# lpm.net
KiCad netlist of a schematic drawn in EAGLE
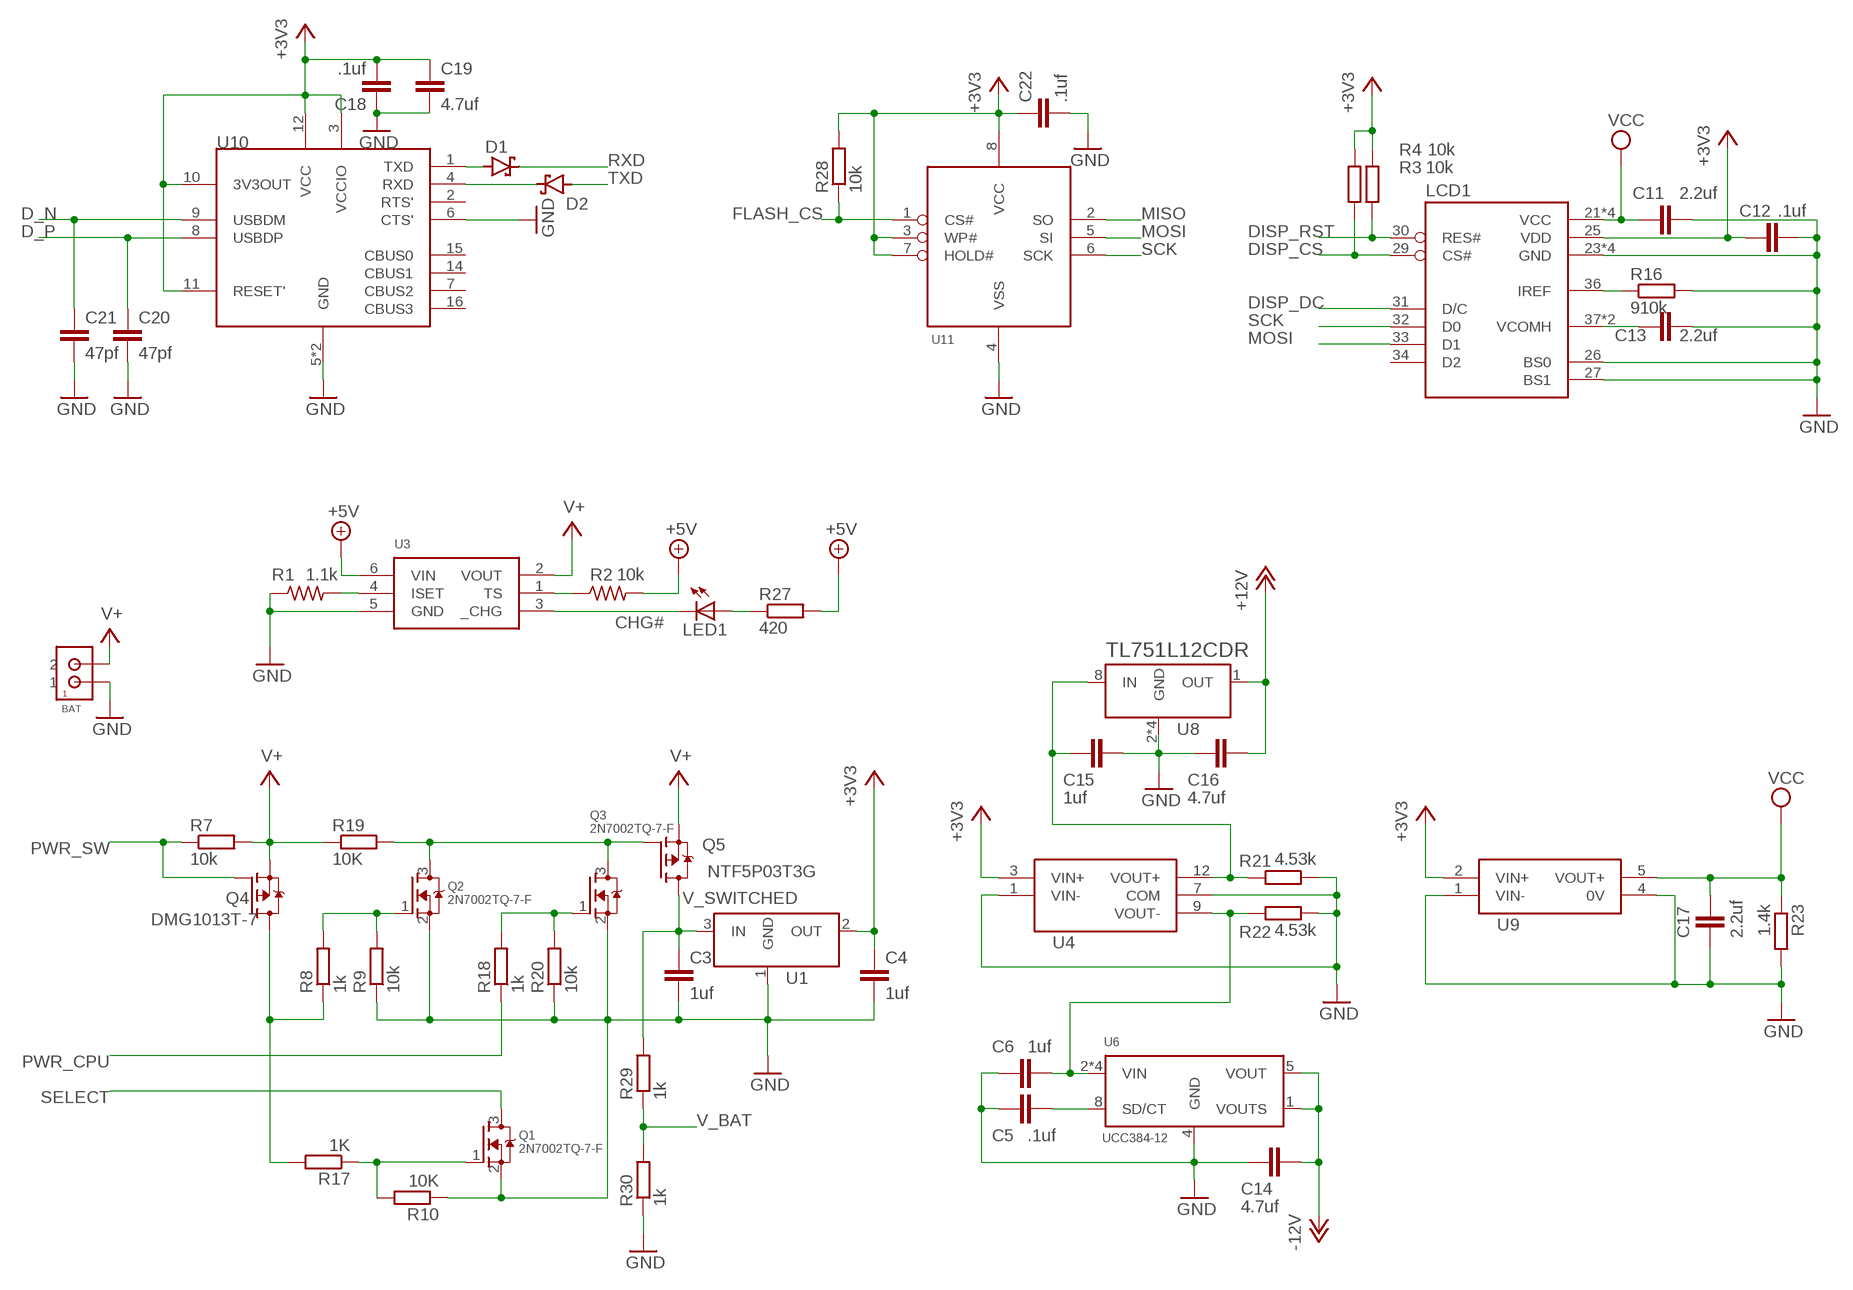
[diagram p0: schematic, sheet 1, part 1 of 2]
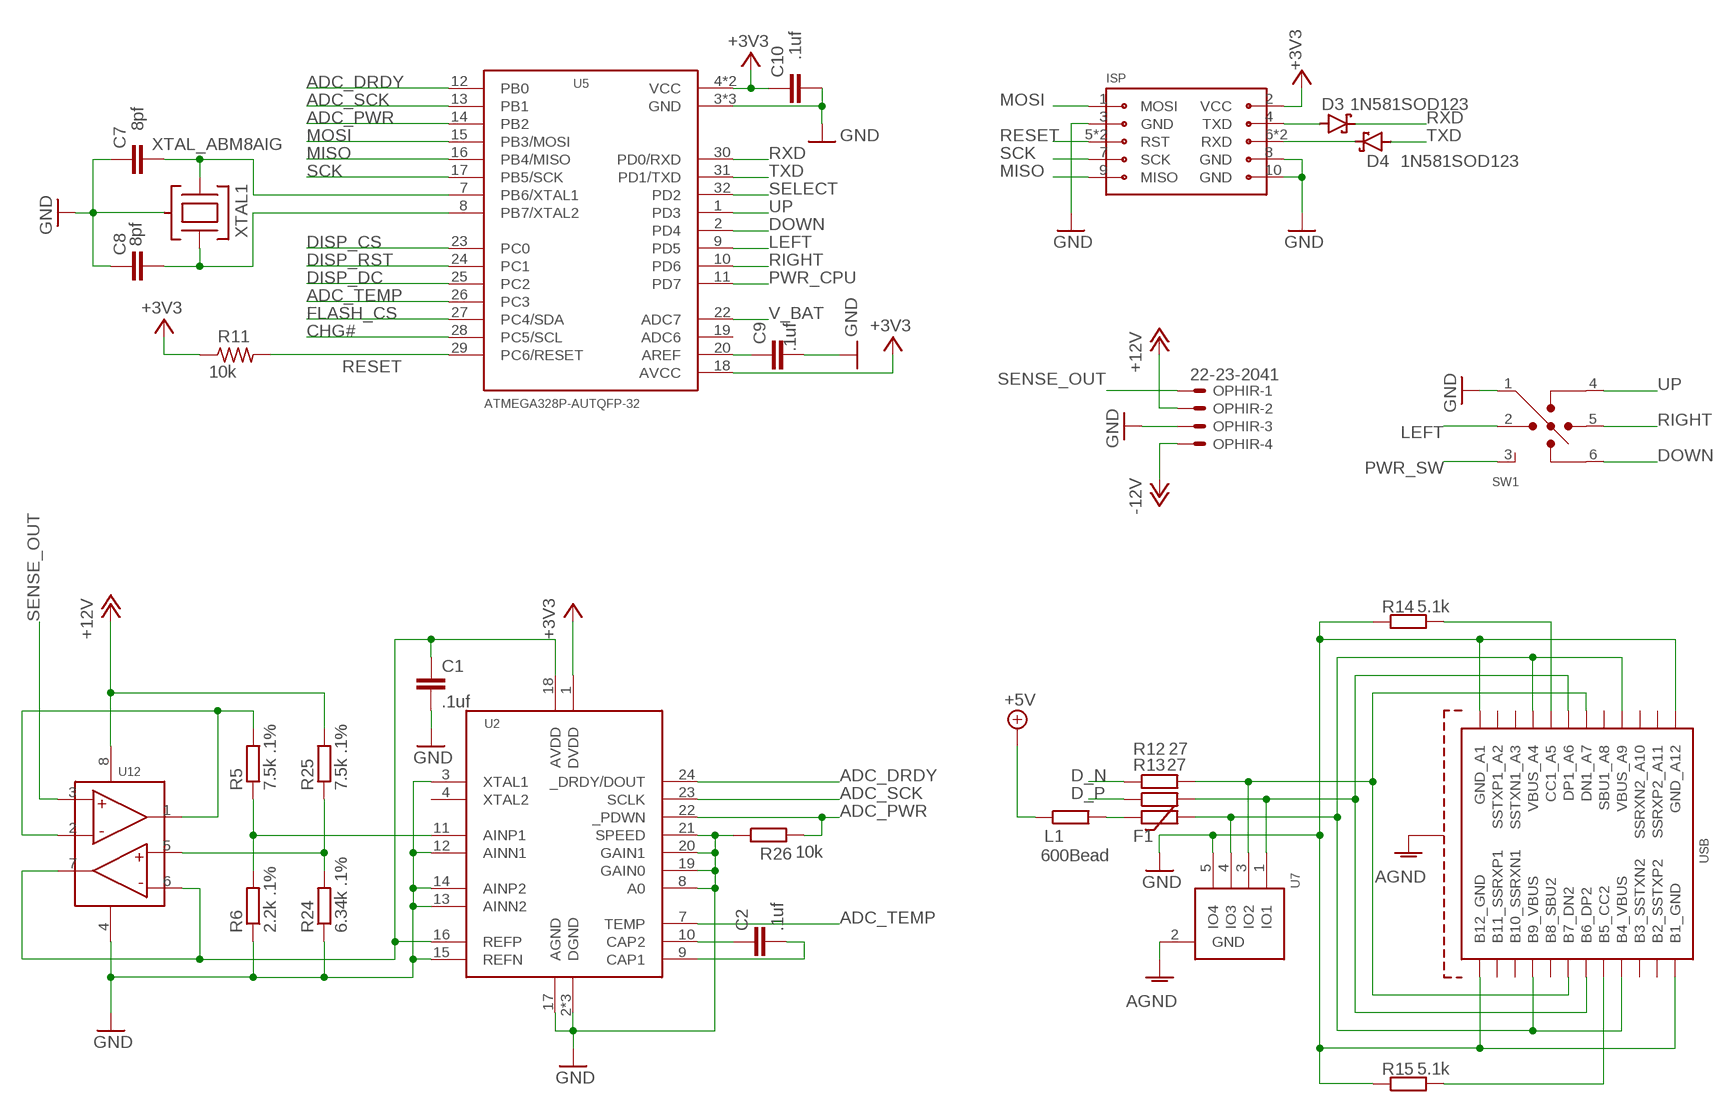
[diagram p1: schematic, sheet 1, part 2 of 2]

(export (version "E")
  (design (tool "Eeschema 10.0.6"))
  (components
    (comp (ref "BAT")
      (value "2PIN_CONNJST_SH")
      (footprint "eagle-import:JST-SM02B-SRSS-TB")
      (libsource (lib "eagle-import") (part "2PIN_CONNJST_SH"))
    )
    (comp (ref "C1")
      (value ".1uf")
      (footprint "eagle-import:C0805")
      (libsource (lib "eagle-import") (part "C-EUC0805"))
    )
    (comp (ref "C2")
      (value ".1uf")
      (footprint "eagle-import:C0805")
      (libsource (lib "eagle-import") (part "C-EUC0805"))
    )
    (comp (ref "C3")
      (value "1uf")
      (footprint "eagle-import:C0805")
      (libsource (lib "eagle-import") (part "C-EUC0805"))
    )
    (comp (ref "C4")
      (value "1uf")
      (footprint "eagle-import:C0805")
      (libsource (lib "eagle-import") (part "C-EUC0805"))
    )
    (comp (ref "C5")
      (value ".1uf")
      (footprint "eagle-import:C0805")
      (libsource (lib "eagle-import") (part "C-EUC0805"))
    )
    (comp (ref "C6")
      (value "1uf")
      (footprint "eagle-import:C0805")
      (libsource (lib "eagle-import") (part "C-EUC0805"))
    )
    (comp (ref "C7")
      (value "8pf")
      (footprint "eagle-import:C0805")
      (libsource (lib "eagle-import") (part "C-EUC0805"))
    )
    (comp (ref "C8")
      (value "8pf")
      (footprint "eagle-import:C0805")
      (libsource (lib "eagle-import") (part "C-EUC0805"))
    )
    (comp (ref "C9")
      (value ".1uf")
      (footprint "eagle-import:C0805")
      (libsource (lib "eagle-import") (part "C-EUC0805"))
    )
    (comp (ref "C10")
      (value ".1uf")
      (footprint "eagle-import:C0805")
      (libsource (lib "eagle-import") (part "C-EUC0805"))
    )
    (comp (ref "C11")
      (value "2.2uf")
      (footprint "eagle-import:C0805")
      (libsource (lib "eagle-import") (part "C-EUC0805"))
    )
    (comp (ref "C12")
      (value ".1uf")
      (footprint "eagle-import:C0805")
      (libsource (lib "eagle-import") (part "C-EUC0805"))
    )
    (comp (ref "C13")
      (value "2.2uf")
      (footprint "eagle-import:C0805")
      (libsource (lib "eagle-import") (part "C-EUC0805"))
    )
    (comp (ref "C14")
      (value "4.7uf")
      (footprint "eagle-import:C0805")
      (libsource (lib "eagle-import") (part "C-EUC0805"))
    )
    (comp (ref "C15")
      (value "1uf")
      (footprint "eagle-import:C0805")
      (libsource (lib "eagle-import") (part "C-EUC0805"))
    )
    (comp (ref "C16")
      (value "4.7uf")
      (footprint "eagle-import:C0805")
      (libsource (lib "eagle-import") (part "C-EUC0805"))
    )
    (comp (ref "C17")
      (value "2.2uf")
      (footprint "eagle-import:C0805")
      (libsource (lib "eagle-import") (part "C-EUC0805"))
    )
    (comp (ref "C18")
      (value ".1uf")
      (footprint "eagle-import:C0805")
      (libsource (lib "eagle-import") (part "C-EUC0805"))
    )
    (comp (ref "C19")
      (value "4.7uf")
      (footprint "eagle-import:C0805")
      (libsource (lib "eagle-import") (part "C-EUC0805"))
    )
    (comp (ref "C20")
      (value "47pf")
      (footprint "eagle-import:C0805")
      (libsource (lib "eagle-import") (part "C-EUC0805"))
    )
    (comp (ref "C21")
      (value "47pf")
      (footprint "eagle-import:C0805")
      (libsource (lib "eagle-import") (part "C-EUC0805"))
    )
    (comp (ref "C22")
      (value ".1uf")
      (footprint "eagle-import:C0805")
      (libsource (lib "eagle-import") (part "C-EUC0805"))
    )
    (comp (ref "D1")
      (value "1N581SOD123")
      (footprint "eagle-import:SOD3715X135")
      (libsource (lib "eagle-import") (part "1N581SOD123"))
    )
    (comp (ref "D2")
      (value "1N581SOD123")
      (footprint "eagle-import:SOD3715X135")
      (libsource (lib "eagle-import") (part "1N581SOD123"))
    )
    (comp (ref "D3")
      (value "1N581SOD123")
      (footprint "eagle-import:SOD3715X135")
      (libsource (lib "eagle-import") (part "1N581SOD123"))
    )
    (comp (ref "D4")
      (value "1N581SOD123")
      (footprint "eagle-import:SOD3715X135")
      (libsource (lib "eagle-import") (part "1N581SOD123"))
    )
    (comp (ref "F1")
      (value "MF-PSHT035KX-2")
      (footprint "eagle-import:FUSC2113X120N")
      (libsource (lib "eagle-import") (part "PTC0805"))
    )
    (comp (ref "ISP")
      (value "10PIN_ISPTC2050")
      (footprint "eagle-import:TC2050-IDC")
      (libsource (lib "eagle-import") (part "10PIN_ISPTC2050"))
    )
    (comp (ref "L1")
      (value "600Bead")
      (footprint "eagle-import:M0805")
      (libsource (lib "eagle-import") (part "R-EU_M0805"))
    )
    (comp (ref "LCD1")
      (value "EAOLEDL128-6")
      (footprint "eagle-import:EAOLEDL128-6")
      (libsource (lib "eagle-import") (part "EAOLEDL128-6"))
    )
    (comp (ref "LED1")
      (value "LEDCHIPLED_0805")
      (footprint "eagle-import:CHIPLED_0805")
      (libsource (lib "eagle-import") (part "LEDCHIPLED_0805"))
    )
    (comp (ref "OPHIR")
      (value "22-23-2041")
      (footprint "eagle-import:22-23-2041")
      (fields (field (name "MF") "MOLEX"))
      (libsource (lib "eagle-import") (part "22-23-2041"))
    )
    (comp (ref "Q1")
      (value "2N7002TQ-7-F")
      (footprint "eagle-import:SOT50P160X80-3")
      (libsource (lib "eagle-import") (part "MOSFET-NSOT-523"))
    )
    (comp (ref "Q2")
      (value "2N7002TQ-7-F")
      (footprint "eagle-import:SOT50P160X80-3")
      (libsource (lib "eagle-import") (part "MOSFET-NSOT-523"))
    )
    (comp (ref "Q3")
      (value "2N7002TQ-7-F")
      (footprint "eagle-import:SOT50P160X80-3")
      (libsource (lib "eagle-import") (part "MOSFET-NSOT-523"))
    )
    (comp (ref "Q4")
      (value "DMG1013T-7")
      (footprint "eagle-import:SOT50P160X80-3")
      (libsource (lib "eagle-import") (part "MOSFET-PSOT-523"))
    )
    (comp (ref "Q5")
      (value "NTF5P03T3G")
      (footprint "eagle-import:SOT230P700X180-4")
      (libsource (lib "eagle-import") (part "MOSFET-PSOT-223"))
    )
    (comp (ref "R1")
      (value "1.1k")
      (footprint "eagle-import:R0805")
      (libsource (lib "eagle-import") (part "R-US_R0805"))
    )
    (comp (ref "R2")
      (value "10k")
      (footprint "eagle-import:R0805")
      (libsource (lib "eagle-import") (part "R-US_R0805"))
    )
    (comp (ref "R3")
      (value "10k")
      (footprint "eagle-import:R0805")
      (libsource (lib "eagle-import") (part "R-EU_R0805"))
    )
    (comp (ref "R4")
      (value "10k")
      (footprint "eagle-import:R0805")
      (libsource (lib "eagle-import") (part "R-EU_R0805"))
    )
    (comp (ref "R5")
      (value "7.5k .1%")
      (footprint "eagle-import:R0805")
      (libsource (lib "eagle-import") (part "R-EU_R0805"))
    )
    (comp (ref "R6")
      (value "2.2k .1%")
      (footprint "eagle-import:R0805")
      (libsource (lib "eagle-import") (part "R-EU_R0805"))
    )
    (comp (ref "R7")
      (value "10k")
      (footprint "eagle-import:R0805")
      (libsource (lib "eagle-import") (part "R-EU_R0805"))
    )
    (comp (ref "R8")
      (value "1k")
      (footprint "eagle-import:R0805")
      (libsource (lib "eagle-import") (part "R-EU_R0805"))
    )
    (comp (ref "R9")
      (value "10k")
      (footprint "eagle-import:R0805")
      (libsource (lib "eagle-import") (part "R-EU_R0805"))
    )
    (comp (ref "R10")
      (value "10K")
      (footprint "eagle-import:R0805")
      (libsource (lib "eagle-import") (part "R-EU_R0805"))
    )
    (comp (ref "R11")
      (value "10k")
      (footprint "eagle-import:R0805")
      (libsource (lib "eagle-import") (part "R-US_R0805"))
    )
    (comp (ref "R12")
      (value "27")
      (footprint "eagle-import:M0805")
      (libsource (lib "eagle-import") (part "R-EU_M0805"))
    )
    (comp (ref "R13")
      (value "27")
      (footprint "eagle-import:M0805")
      (libsource (lib "eagle-import") (part "R-EU_M0805"))
    )
    (comp (ref "R14")
      (value "5.1k")
      (footprint "eagle-import:M0805")
      (libsource (lib "eagle-import") (part "R-EU_M0805"))
    )
    (comp (ref "R15")
      (value "5.1k")
      (footprint "eagle-import:M0805")
      (libsource (lib "eagle-import") (part "R-EU_M0805"))
    )
    (comp (ref "R16")
      (value "910k")
      (footprint "eagle-import:R0805")
      (libsource (lib "eagle-import") (part "R-EU_R0805"))
    )
    (comp (ref "R17")
      (value "1K")
      (footprint "eagle-import:R0805")
      (libsource (lib "eagle-import") (part "R-EU_R0805"))
    )
    (comp (ref "R18")
      (value "1k")
      (footprint "eagle-import:R0805")
      (libsource (lib "eagle-import") (part "R-EU_R0805"))
    )
    (comp (ref "R19")
      (value "10K")
      (footprint "eagle-import:R0805")
      (libsource (lib "eagle-import") (part "R-EU_R0805"))
    )
    (comp (ref "R20")
      (value "10k")
      (footprint "eagle-import:R0805")
      (libsource (lib "eagle-import") (part "R-EU_R0805"))
    )
    (comp (ref "R21")
      (value "4.53k")
      (footprint "eagle-import:R0805")
      (libsource (lib "eagle-import") (part "R-EU_R0805"))
    )
    (comp (ref "R22")
      (value "4.53k")
      (footprint "eagle-import:R0805")
      (libsource (lib "eagle-import") (part "R-EU_R0805"))
    )
    (comp (ref "R23")
      (value "1.4k")
      (footprint "eagle-import:R0805")
      (libsource (lib "eagle-import") (part "R-EU_R0805"))
    )
    (comp (ref "R24")
      (value "6.34k .1%")
      (footprint "eagle-import:R0805")
      (libsource (lib "eagle-import") (part "R-EU_R0805"))
    )
    (comp (ref "R25")
      (value "7.5k .1%")
      (footprint "eagle-import:R0805")
      (libsource (lib "eagle-import") (part "R-EU_R0805"))
    )
    (comp (ref "R26")
      (value "10k")
      (footprint "eagle-import:R0805")
      (libsource (lib "eagle-import") (part "R-EU_R0805"))
    )
    (comp (ref "R27")
      (value "420")
      (footprint "eagle-import:R0805")
      (libsource (lib "eagle-import") (part "R-EU_R0805"))
    )
    (comp (ref "R28")
      (value "10k")
      (footprint "eagle-import:R0805")
      (libsource (lib "eagle-import") (part "R-EU_R0805"))
    )
    (comp (ref "R29")
      (value "1k")
      (footprint "eagle-import:R0805")
      (libsource (lib "eagle-import") (part "R-EU_R0805"))
    )
    (comp (ref "R30")
      (value "1k")
      (footprint "eagle-import:R0805")
      (libsource (lib "eagle-import") (part "R-EU_R0805"))
    )
    (comp (ref "SW1")
      (value "JS-5208")
      (footprint "eagle-import:JS-5208")
      (libsource (lib "eagle-import") (part "JS-5208"))
    )
    (comp (ref "U1")
      (value "AZ1117E-3.3SOT-223")
      (footprint "eagle-import:SOT230P700X180-4")
      (libsource (lib "eagle-import") (part "AZ1117E-3.3SOT-223"))
    )
    (comp (ref "U2")
      (value "ADS1232")
      (footprint "eagle-import:SOP65P640X120-24")
      (libsource (lib "eagle-import") (part "ADS1232"))
    )
    (comp (ref "U3")
      (value "BQ21040SOT-23")
      (footprint "eagle-import:SOT95P280X145-6")
      (libsource (lib "eagle-import") (part "BQ21040SOT-23"))
    )
    (comp (ref "U4")
      (value "NTA0315MC-R")
      (footprint "eagle-import:NTA0315MC-R")
      (libsource (lib "eagle-import") (part "NTA0315MC-R"))
    )
    (comp (ref "U5")
      (value "ATMEGA328P-AUTQFP-32")
      (footprint "eagle-import:QFP80P887X887X120-32")
      (libsource (lib "eagle-import") (part "ATMEGA328P-AUTQFP-32"))
    )
    (comp (ref "U6")
      (value "UCC384-12")
      (footprint "eagle-import:SOIC127P599X175-8")
      (libsource (lib "eagle-import") (part "UCC384-X"))
    )
    (comp (ref "U7")
      (value "ESDS314")
      (footprint "eagle-import:SOT95P282X145-5")
      (libsource (lib "eagle-import") (part "ESDS314"))
    )
    (comp (ref "U8")
      (value "TL751L12CDR")
      (footprint "eagle-import:SOIC127P599X175-8")
      (libsource (lib "eagle-import") (part "TL751"))
    )
    (comp (ref "U9")
      (value "ISE0312A")
      (footprint "eagle-import:ISE0312A")
      (libsource (lib "eagle-import") (part "ISE312A"))
    )
    (comp (ref "U10")
      (value "FT230XSSOP16")
      (footprint "eagle-import:SOP63P599X175-16")
      (libsource (lib "eagle-import") (part "FT230XSSOP16"))
    )
    (comp (ref "U11")
      (value "NV25640DWHFT3G")
      (footprint "eagle-import:SOIC127P599X175-8")
      (libsource (lib "eagle-import") (part "NV25640SOIC-8"))
    )
    (comp (ref "U12")
      (value "OPA2210VSSOP8")
      (footprint "eagle-import:SOP65P490X110-8")
      (libsource (lib "eagle-import") (part "OPA2210VSSOP8"))
    )
    (comp (ref "USB")
      (value "USBC_FEMALEUJ31-CH-31-SMT-TR")
      (footprint "eagle-import:USBC_UJ31-CH-31-SMT-TR")
      (libsource (lib "eagle-import") (part "USBC_FEMALEUJ31-CH-31-SMT-TR"))
    )
    (comp (ref "XTAL1")
      (value "XTAL_ABM8AIG")
      (footprint "eagle-import:XTAL_SMT_3.2X2.5")
      (libsource (lib "eagle-import") (part "XTAL_ABM8AIG"))
    )
  )
  (nets
    (net (code "1") (name "+3V3") (class "Default")
      (node (ref "C10") (pin "1") (pinfunction "1_1") (pintype "passive"))
      (node (ref "C12") (pin "1") (pinfunction "1_1") (pintype "passive"))
      (node (ref "C18") (pin "2") (pinfunction "2_2") (pintype "passive"))
      (node (ref "C19") (pin "1") (pinfunction "1_1") (pintype "passive"))
      (node (ref "C22") (pin "1") (pinfunction "1_1") (pintype "passive"))
      (node (ref "C4") (pin "1") (pinfunction "1_1") (pintype "passive"))
      (node (ref "ISP") (pin "2") (pinfunction "VCC_2") (pintype "bidirectional"))
      (node (ref "LCD1") (pin "25") (pinfunction "VDD_25") (pintype "power_in"))
      (node (ref "R11") (pin "1") (pinfunction "1_1") (pintype "passive"))
      (node (ref "R28") (pin "2") (pinfunction "2_2") (pintype "passive"))
      (node (ref "R3") (pin "2") (pinfunction "2_2") (pintype "passive"))
      (node (ref "R4") (pin "2") (pinfunction "2_2") (pintype "passive"))
      (node (ref "U1") (pin "2") (pinfunction "OUT_2") (pintype "power_in"))
      (node (ref "U10") (pin "10") (pinfunction "3V3OUT_10") (pintype "bidirectional"))
      (node (ref "U10") (pin "11") (pinfunction "RESET'_11") (pintype "bidirectional"))
      (node (ref "U10") (pin "12") (pinfunction "VCC_12") (pintype "power_in"))
      (node (ref "U10") (pin "3") (pinfunction "VCCIO_3") (pintype "power_in"))
      (node (ref "U11") (pin "3") (pinfunction "WP#_3") (pintype "bidirectional"))
      (node (ref "U11") (pin "7") (pinfunction "HOLD#_7") (pintype "bidirectional"))
      (node (ref "U11") (pin "8") (pinfunction "VCC_8") (pintype "power_in"))
      (node (ref "U2") (pin "1") (pinfunction "DVDD_1") (pintype "power_in"))
      (node (ref "U4") (pin "3") (pinfunction "VIN+_3") (pintype "power_in"))
      (node (ref "U5") (pin "18") (pinfunction "AVCC_18") (pintype "power_in"))
      (node (ref "U5") (pin "4") (pinfunction "VCC_4") (pintype "power_in"))
      (node (ref "U5") (pin "6") (pinfunction "VCC_6") (pintype "power_in"))
      (node (ref "U9") (pin "2") (pinfunction "VIN+_2") (pintype "power_in"))
    )
    (net (code "2") (name "+5V") (class "Default")
      (node (ref "L1") (pin "1") (pinfunction "1_1") (pintype "passive"))
      (node (ref "R2") (pin "2") (pinfunction "2_2") (pintype "passive"))
      (node (ref "R27") (pin "2") (pinfunction "2_2") (pintype "passive"))
      (node (ref "U3") (pin "6") (pinfunction "VIN_6") (pintype "power_in"))
    )
    (net (code "3") (name "+12V") (class "Default")
      (node (ref "C16") (pin "2") (pinfunction "2_2") (pintype "passive"))
      (node (ref "OPHIR") (pin "2") (pinfunction "S_2") (pintype "passive"))
      (node (ref "R25") (pin "2") (pinfunction "2_2") (pintype "passive"))
      (node (ref "U12") (pin "8") (pinfunction "V+_8") (pintype "power_in"))
      (node (ref "U8") (pin "1") (pinfunction "OUT_1") (pintype "power_in"))
    )
    (net (code "4") (name "-12V") (class "Default")
      (node (ref "C14") (pin "2") (pinfunction "2_2") (pintype "passive"))
      (node (ref "OPHIR") (pin "4") (pinfunction "S_4") (pintype "passive"))
      (node (ref "U6") (pin "1") (pinfunction "VOUTS_1") (pintype "bidirectional"))
      (node (ref "U6") (pin "5") (pinfunction "VOUT_5") (pintype "power_in"))
    )
    (net (code "5") (name "/ADC_DRDY") (class "Default")
      (node (ref "U2") (pin "24") (pinfunction "_DRDY/DOUT_24") (pintype "bidirectional"))
      (node (ref "U5") (pin "12") (pinfunction "PB0_12") (pintype "bidirectional"))
    )
    (net (code "6") (name "/ADC_PWR") (class "Default")
      (node (ref "R26") (pin "2") (pinfunction "2_2") (pintype "passive"))
      (node (ref "U2") (pin "22") (pinfunction "_PDWN_22") (pintype "bidirectional"))
      (node (ref "U5") (pin "14") (pinfunction "PB2_14") (pintype "bidirectional"))
    )
    (net (code "7") (name "/ADC_SCK") (class "Default")
      (node (ref "U2") (pin "23") (pinfunction "SCLK_23") (pintype "bidirectional"))
      (node (ref "U5") (pin "13") (pinfunction "PB1_13") (pintype "bidirectional"))
    )
    (net (code "8") (name "/ADC_TEMP") (class "Default")
      (node (ref "U2") (pin "7") (pinfunction "TEMP_7") (pintype "bidirectional"))
      (node (ref "U5") (pin "26") (pinfunction "PC3_26") (pintype "bidirectional"))
    )
    (net (code "9") (name "/CHG#") (class "Default")
      (node (ref "LED1") (pin "C") (pinfunction "C_C") (pintype "passive"))
      (node (ref "U3") (pin "3") (pinfunction "_CHG_3") (pintype "bidirectional"))
      (node (ref "U5") (pin "28") (pinfunction "PC5/SCL_28") (pintype "bidirectional"))
    )
    (net (code "10") (name "/DISP_CS") (class "Default")
      (node (ref "LCD1") (pin "29") (pinfunction "CS#_29") (pintype "bidirectional"))
      (node (ref "R4") (pin "1") (pinfunction "1_1") (pintype "passive"))
      (node (ref "U5") (pin "23") (pinfunction "PC0_23") (pintype "bidirectional"))
    )
    (net (code "11") (name "/DISP_DC") (class "Default")
      (node (ref "LCD1") (pin "31") (pinfunction "D/C_31") (pintype "bidirectional"))
      (node (ref "U5") (pin "25") (pinfunction "PC2_25") (pintype "bidirectional"))
    )
    (net (code "12") (name "/DISP_RST") (class "Default")
      (node (ref "LCD1") (pin "30") (pinfunction "RES#_30") (pintype "bidirectional"))
      (node (ref "R3") (pin "1") (pinfunction "1_1") (pintype "passive"))
      (node (ref "U5") (pin "24") (pinfunction "PC1_24") (pintype "bidirectional"))
    )
    (net (code "13") (name "/DOWN") (class "Default")
      (node (ref "SW1") (pin "6") (pinfunction "D_6") (pintype "bidirectional"))
      (node (ref "U5") (pin "2") (pinfunction "PD4_2") (pintype "bidirectional"))
    )
    (net (code "14") (name "/D_N") (class "Default")
      (node (ref "C21") (pin "1") (pinfunction "1_1") (pintype "passive"))
      (node (ref "R12") (pin "1") (pinfunction "1_1") (pintype "passive"))
      (node (ref "U10") (pin "9") (pinfunction "USBDM_9") (pintype "bidirectional"))
    )
    (net (code "15") (name "/D_P") (class "Default")
      (node (ref "C20") (pin "1") (pinfunction "1_1") (pintype "passive"))
      (node (ref "R13") (pin "1") (pinfunction "1_1") (pintype "passive"))
      (node (ref "U10") (pin "8") (pinfunction "USBDP_8") (pintype "bidirectional"))
    )
    (net (code "16") (name "/FLASH_CS") (class "Default")
      (node (ref "R28") (pin "1") (pinfunction "1_1") (pintype "passive"))
      (node (ref "U11") (pin "1") (pinfunction "CS#_1") (pintype "bidirectional"))
      (node (ref "U5") (pin "27") (pinfunction "PC4/SDA_27") (pintype "bidirectional"))
    )
    (net (code "17") (name "/LEFT") (class "Default")
      (node (ref "SW1") (pin "2") (pinfunction "L_2") (pintype "bidirectional"))
      (node (ref "U5") (pin "9") (pinfunction "PD5_9") (pintype "bidirectional"))
    )
    (net (code "18") (name "/MISO") (class "Default")
      (node (ref "ISP") (pin "9") (pinfunction "MISO_9") (pintype "bidirectional"))
      (node (ref "U11") (pin "2") (pinfunction "SO_2") (pintype "bidirectional"))
      (node (ref "U5") (pin "16") (pinfunction "PB4/MISO_16") (pintype "bidirectional"))
    )
    (net (code "19") (name "/MOSI") (class "Default")
      (node (ref "ISP") (pin "1") (pinfunction "MOSI_1") (pintype "bidirectional"))
      (node (ref "LCD1") (pin "33") (pinfunction "D1_33") (pintype "bidirectional"))
      (node (ref "U11") (pin "5") (pinfunction "SI_5") (pintype "bidirectional"))
      (node (ref "U5") (pin "15") (pinfunction "PB3/MOSI_15") (pintype "bidirectional"))
    )
    (net (code "20") (name "/PWR_CPU") (class "Default")
      (node (ref "R18") (pin "1") (pinfunction "1_1") (pintype "passive"))
      (node (ref "U5") (pin "11") (pinfunction "PD7_11") (pintype "bidirectional"))
    )
    (net (code "21") (name "/PWR_SW") (class "Default")
      (node (ref "Q4") (pin "1") (pinfunction "G_1") (pintype "passive"))
      (node (ref "R7") (pin "1") (pinfunction "1_1") (pintype "passive"))
      (node (ref "SW1") (pin "3") (pinfunction "P_3") (pintype "bidirectional"))
    )
    (net (code "22") (name "/RESET") (class "Default")
      (node (ref "ISP") (pin "5") (pinfunction "RST_5") (pintype "bidirectional"))
      (node (ref "ISP") (pin "L5") (pinfunction "RST_L5") (pintype "bidirectional"))
      (node (ref "R11") (pin "2") (pinfunction "2_2") (pintype "passive"))
      (node (ref "U5") (pin "29") (pinfunction "PC6/RESET_29") (pintype "bidirectional"))
    )
    (net (code "23") (name "/RIGHT") (class "Default")
      (node (ref "SW1") (pin "5") (pinfunction "R_5") (pintype "bidirectional"))
      (node (ref "U5") (pin "10") (pinfunction "PD6_10") (pintype "bidirectional"))
    )
    (net (code "24") (name "/RXD") (class "Default")
      (node (ref "D1") (pin "C") (pinfunction "C_C") (pintype "passive"))
      (node (ref "D3") (pin "C") (pinfunction "C_C") (pintype "passive"))
      (node (ref "U5") (pin "30") (pinfunction "PD0/RXD_30") (pintype "bidirectional"))
    )
    (net (code "25") (name "/SCK") (class "Default")
      (node (ref "ISP") (pin "7") (pinfunction "SCK_7") (pintype "bidirectional"))
      (node (ref "LCD1") (pin "32") (pinfunction "D0_32") (pintype "bidirectional"))
      (node (ref "U11") (pin "6") (pinfunction "SCK_6") (pintype "bidirectional"))
      (node (ref "U5") (pin "17") (pinfunction "PB5/SCK_17") (pintype "bidirectional"))
    )
    (net (code "26") (name "/SELECT") (class "Default")
      (node (ref "Q1") (pin "3") (pinfunction "D_3") (pintype "bidirectional"))
      (node (ref "U5") (pin "32") (pinfunction "PD2_32") (pintype "bidirectional"))
    )
    (net (code "27") (name "/SENSE_OUT") (class "Default")
      (node (ref "OPHIR") (pin "1") (pinfunction "S_1") (pintype "passive"))
      (node (ref "U12") (pin "3") (pinfunction "IN1+_3") (pintype "bidirectional"))
    )
    (net (code "28") (name "/TXD") (class "Default")
      (node (ref "D2") (pin "A") (pinfunction "A_A") (pintype "passive"))
      (node (ref "D4") (pin "A") (pinfunction "A_A") (pintype "passive"))
      (node (ref "U5") (pin "31") (pinfunction "PD1/TXD_31") (pintype "bidirectional"))
    )
    (net (code "29") (name "/UP") (class "Default")
      (node (ref "SW1") (pin "4") (pinfunction "U_4") (pintype "bidirectional"))
      (node (ref "U5") (pin "1") (pinfunction "PD3_1") (pintype "bidirectional"))
    )
    (net (code "30") (name "/V_BAT") (class "Default")
      (node (ref "R29") (pin "1") (pinfunction "1_1") (pintype "passive"))
      (node (ref "R30") (pin "2") (pinfunction "2_2") (pintype "passive"))
      (node (ref "U5") (pin "22") (pinfunction "ADC7_22") (pintype "bidirectional"))
    )
    (net (code "31") (name "/V_SWITCHED") (class "Default")
      (node (ref "C3") (pin "1") (pinfunction "1_1") (pintype "passive"))
      (node (ref "Q5") (pin "2") (pinfunction "D_2") (pintype "passive"))
      (node (ref "Q5") (pin "4") (pinfunction "D_4") (pintype "passive"))
      (node (ref "R29") (pin "2") (pinfunction "2_2") (pintype "passive"))
      (node (ref "U1") (pin "3") (pinfunction "IN_3") (pintype "power_in"))
    )
    (net (code "32") (name "AGND") (class "Default")
      (node (ref "U7") (pin "2") (pinfunction "GND_2") (pintype "power_in"))
      (node (ref "USB") (pin "SHLD@1") (pinfunction "SHLD_SHLD@1") (pintype "power_in"))
      (node (ref "USB") (pin "SHLD@2") (pinfunction "SHLD_SHLD@2") (pintype "power_in"))
      (node (ref "USB") (pin "SHLD@3") (pinfunction "SHLD_SHLD@3") (pintype "power_in"))
      (node (ref "USB") (pin "SHLD@4") (pinfunction "SHLD_SHLD@4") (pintype "power_in"))
      (node (ref "USB") (pin "SHLD@5") (pinfunction "SHLD_SHLD@5") (pintype "power_in"))
      (node (ref "USB") (pin "SHLD@6") (pinfunction "SHLD_SHLD@6") (pintype "power_in"))
      (node (ref "USB") (pin "SHLD@7") (pinfunction "SHLD_SHLD@7") (pintype "power_in"))
      (node (ref "USB") (pin "SHLD@8") (pinfunction "SHLD_SHLD@8") (pintype "power_in"))
    )
    (net (code "33") (name "GND") (class "Default")
      (node (ref "BAT") (pin "1") (pinfunction "1_1") (pintype "bidirectional"))
      (node (ref "C1") (pin "2") (pinfunction "2_2") (pintype "passive"))
      (node (ref "C10") (pin "2") (pinfunction "2_2") (pintype "passive"))
      (node (ref "C11") (pin "2") (pinfunction "2_2") (pintype "passive"))
      (node (ref "C12") (pin "2") (pinfunction "2_2") (pintype "passive"))
      (node (ref "C13") (pin "2") (pinfunction "2_2") (pintype "passive"))
      (node (ref "C14") (pin "1") (pinfunction "1_1") (pintype "passive"))
      (node (ref "C15") (pin "2") (pinfunction "2_2") (pintype "passive"))
      (node (ref "C16") (pin "1") (pinfunction "1_1") (pintype "passive"))
      (node (ref "C17") (pin "2") (pinfunction "2_2") (pintype "passive"))
      (node (ref "C18") (pin "1") (pinfunction "1_1") (pintype "passive"))
      (node (ref "C19") (pin "2") (pinfunction "2_2") (pintype "passive"))
      (node (ref "C20") (pin "2") (pinfunction "2_2") (pintype "passive"))
      (node (ref "C21") (pin "2") (pinfunction "2_2") (pintype "passive"))
      (node (ref "C22") (pin "2") (pinfunction "2_2") (pintype "passive"))
      (node (ref "C3") (pin "2") (pinfunction "2_2") (pintype "passive"))
      (node (ref "C4") (pin "2") (pinfunction "2_2") (pintype "passive"))
      (node (ref "C5") (pin "1") (pinfunction "1_1") (pintype "passive"))
      (node (ref "C6") (pin "1") (pinfunction "1_1") (pintype "passive"))
      (node (ref "C7") (pin "1") (pinfunction "1_1") (pintype "passive"))
      (node (ref "C8") (pin "1") (pinfunction "1_1") (pintype "passive"))
      (node (ref "C9") (pin "2") (pinfunction "2_2") (pintype "passive"))
      (node (ref "ISP") (pin "10") (pinfunction "GND_10") (pintype "bidirectional"))
      (node (ref "ISP") (pin "3") (pinfunction "GND_3") (pintype "bidirectional"))
      (node (ref "ISP") (pin "8") (pinfunction "GND_8") (pintype "bidirectional"))
      (node (ref "LCD1") (pin "23") (pinfunction "GND_23") (pintype "power_in"))
      (node (ref "LCD1") (pin "24") (pinfunction "GND_24") (pintype "power_in"))
      (node (ref "LCD1") (pin "26") (pinfunction "BS0_26") (pintype "bidirectional"))
      (node (ref "LCD1") (pin "27") (pinfunction "BS1_27") (pintype "bidirectional"))
      (node (ref "LCD1") (pin "28") (pinfunction "GND_28") (pintype "power_in"))
      (node (ref "LCD1") (pin "35") (pinfunction "GND_35") (pintype "power_in"))
      (node (ref "OPHIR") (pin "3") (pinfunction "S_3") (pintype "passive"))
      (node (ref "Q1") (pin "2") (pinfunction "S_2") (pintype "bidirectional"))
      (node (ref "Q2") (pin "2") (pinfunction "S_2") (pintype "bidirectional"))
      (node (ref "Q3") (pin "2") (pinfunction "S_2") (pintype "bidirectional"))
      (node (ref "R1") (pin "1") (pinfunction "1_1") (pintype "passive"))
      (node (ref "R10") (pin "1") (pinfunction "1_1") (pintype "passive"))
      (node (ref "R14") (pin "1") (pinfunction "1_1") (pintype "passive"))
      (node (ref "R15") (pin "1") (pinfunction "1_1") (pintype "passive"))
      (node (ref "R16") (pin "2") (pinfunction "2_2") (pintype "passive"))
      (node (ref "R20") (pin "1") (pinfunction "1_1") (pintype "passive"))
      (node (ref "R21") (pin "2") (pinfunction "2_2") (pintype "passive"))
      (node (ref "R22") (pin "2") (pinfunction "2_2") (pintype "passive"))
      (node (ref "R23") (pin "2") (pinfunction "2_2") (pintype "passive"))
      (node (ref "R24") (pin "1") (pinfunction "1_1") (pintype "passive"))
      (node (ref "R26") (pin "1") (pinfunction "1_1") (pintype "passive"))
      (node (ref "R30") (pin "1") (pinfunction "1_1") (pintype "passive"))
      (node (ref "R6") (pin "1") (pinfunction "1_1") (pintype "passive"))
      (node (ref "R9") (pin "1") (pinfunction "1_1") (pintype "passive"))
      (node (ref "SW1") (pin "1") (pinfunction "C_1") (pintype "bidirectional"))
      (node (ref "U1") (pin "1") (pinfunction "GND_1") (pintype "power_in"))
      (node (ref "U10") (pin "13") (pinfunction "GND_13") (pintype "power_in"))
      (node (ref "U10") (pin "5") (pinfunction "GND_5") (pintype "power_in"))
      (node (ref "U10") (pin "6") (pinfunction "CTS'_6") (pintype "bidirectional"))
      (node (ref "U11") (pin "4") (pinfunction "VSS_4") (pintype "power_in"))
      (node (ref "U12") (pin "4") (pinfunction "V-_4") (pintype "power_in"))
      (node (ref "U2") (pin "12") (pinfunction "AINN1_12") (pintype "bidirectional"))
      (node (ref "U2") (pin "13") (pinfunction "AINN2_13") (pintype "bidirectional"))
      (node (ref "U2") (pin "14") (pinfunction "AINP2_14") (pintype "bidirectional"))
      (node (ref "U2") (pin "15") (pinfunction "REFN_15") (pintype "bidirectional"))
      (node (ref "U2") (pin "17") (pinfunction "AGND_17") (pintype "power_in"))
      (node (ref "U2") (pin "19") (pinfunction "GAIN0_19") (pintype "bidirectional"))
      (node (ref "U2") (pin "2") (pinfunction "DGND_2") (pintype "power_in"))
      (node (ref "U2") (pin "20") (pinfunction "GAIN1_20") (pintype "bidirectional"))
      (node (ref "U2") (pin "21") (pinfunction "SPEED_21") (pintype "bidirectional"))
      (node (ref "U2") (pin "3") (pinfunction "XTAL1_3") (pintype "bidirectional"))
      (node (ref "U2") (pin "5") (pinfunction "DGND_5") (pintype "power_in"))
      (node (ref "U2") (pin "6") (pinfunction "DGND_6") (pintype "power_in"))
      (node (ref "U2") (pin "8") (pinfunction "A0_8") (pintype "bidirectional"))
      (node (ref "U3") (pin "5") (pinfunction "GND_5") (pintype "power_in"))
      (node (ref "U4") (pin "1") (pinfunction "VIN-_1") (pintype "power_in"))
      (node (ref "U4") (pin "7") (pinfunction "COM_7") (pintype "power_in"))
      (node (ref "U5") (pin "21") (pinfunction "GND_21") (pintype "power_in"))
      (node (ref "U5") (pin "3") (pinfunction "GND_3") (pintype "power_in"))
      (node (ref "U5") (pin "5") (pinfunction "GND_5") (pintype "power_in"))
      (node (ref "U6") (pin "4") (pinfunction "GND_4") (pintype "bidirectional"))
      (node (ref "U7") (pin "5") (pinfunction "IO4_5") (pintype "bidirectional"))
      (node (ref "U8") (pin "2") (pinfunction "GND_2") (pintype "power_in"))
      (node (ref "U8") (pin "3") (pinfunction "GND_3") (pintype "power_in"))
      (node (ref "U8") (pin "6") (pinfunction "GND_6") (pintype "power_in"))
      (node (ref "U8") (pin "7") (pinfunction "GND_7") (pintype "power_in"))
      (node (ref "U9") (pin "1") (pinfunction "VIN-_1") (pintype "power_in"))
      (node (ref "U9") (pin "4") (pinfunction "0V_4") (pintype "power_in"))
      (node (ref "USB") (pin "A1") (pinfunction "GND_A1_A1") (pintype "power_in"))
      (node (ref "USB") (pin "A12") (pinfunction "GND_A12_A12") (pintype "power_in"))
      (node (ref "USB") (pin "B1") (pinfunction "B1_GND_B1") (pintype "power_in"))
      (node (ref "USB") (pin "B12") (pinfunction "B12_GND_B12") (pintype "power_in"))
      (node (ref "XTAL1") (pin "2") (pinfunction "CASE_2") (pintype "bidirectional"))
      (node (ref "XTAL1") (pin "4") (pinfunction "CASE_4") (pintype "bidirectional"))
    )
    (net (code "34") (name "Net-(C13-Pad1)") (class "Default")
      (node (ref "C13") (pin "1") (pinfunction "1_1") (pintype "passive"))
      (node (ref "LCD1") (pin "37") (pinfunction "VCOMH_37") (pintype "bidirectional"))
      (node (ref "LCD1") (pin "38") (pinfunction "VCOMH_38") (pintype "bidirectional"))
    )
    (net (code "35") (name "Net-(D4-PadC)") (class "Default")
      (node (ref "D4") (pin "C") (pinfunction "C_C") (pintype "passive"))
      (node (ref "ISP") (pin "6") (pinfunction "RXD_6") (pintype "bidirectional"))
      (node (ref "ISP") (pin "L6") (pinfunction "RXD_L6") (pintype "bidirectional"))
    )
    (net (code "36") (name "Net-(F1-Pad1)") (class "Default")
      (node (ref "F1") (pin "1") (pinfunction "1_1") (pintype "passive"))
      (node (ref "L1") (pin "2") (pinfunction "2_2") (pintype "passive"))
    )
    (net (code "37") (name "Net-(ISP-TXD)") (class "Default")
      (node (ref "D3") (pin "A") (pinfunction "A_A") (pintype "passive"))
      (node (ref "ISP") (pin "4") (pinfunction "TXD_4") (pintype "bidirectional"))
    )
    (net (code "38") (name "Net-(LCD1-IREF)") (class "Default")
      (node (ref "LCD1") (pin "36") (pinfunction "IREF_36") (pintype "bidirectional"))
      (node (ref "R16") (pin "1") (pinfunction "1_1") (pintype "passive"))
    )
    (net (code "39") (name "Net-(LED1-PadA)") (class "Default")
      (node (ref "LED1") (pin "A") (pinfunction "A_A") (pintype "passive"))
      (node (ref "R27") (pin "1") (pinfunction "1_1") (pintype "passive"))
    )
    (net (code "40") (name "Net-(Q1-G)") (class "Default")
      (node (ref "Q1") (pin "1") (pinfunction "G_1") (pintype "bidirectional"))
      (node (ref "R10") (pin "2") (pinfunction "2_2") (pintype "passive"))
      (node (ref "R17") (pin "1") (pinfunction "1_1") (pintype "passive"))
    )
    (net (code "41") (name "Net-(Q2-D)") (class "Default")
      (node (ref "Q2") (pin "3") (pinfunction "D_3") (pintype "bidirectional"))
      (node (ref "Q3") (pin "3") (pinfunction "D_3") (pintype "bidirectional"))
      (node (ref "Q5") (pin "1") (pinfunction "G_1") (pintype "passive"))
      (node (ref "R19") (pin "2") (pinfunction "2_2") (pintype "passive"))
    )
    (net (code "42") (name "Net-(Q2-G)") (class "Default")
      (node (ref "Q2") (pin "1") (pinfunction "G_1") (pintype "bidirectional"))
      (node (ref "R8") (pin "2") (pinfunction "2_2") (pintype "passive"))
      (node (ref "R9") (pin "2") (pinfunction "2_2") (pintype "passive"))
    )
    (net (code "43") (name "Net-(Q3-G)") (class "Default")
      (node (ref "Q3") (pin "1") (pinfunction "G_1") (pintype "bidirectional"))
      (node (ref "R18") (pin "2") (pinfunction "2_2") (pintype "passive"))
      (node (ref "R20") (pin "2") (pinfunction "2_2") (pintype "passive"))
    )
    (net (code "44") (name "Net-(Q4-D)") (class "Default")
      (node (ref "Q4") (pin "3") (pinfunction "D_3") (pintype "passive"))
      (node (ref "R17") (pin "2") (pinfunction "2_2") (pintype "passive"))
      (node (ref "R8") (pin "1") (pinfunction "1_1") (pintype "passive"))
    )
    (net (code "45") (name "Net-(U2-AINP1)") (class "Default")
      (node (ref "R5") (pin "1") (pinfunction "1_1") (pintype "passive"))
      (node (ref "R6") (pin "2") (pinfunction "2_2") (pintype "passive"))
      (node (ref "U2") (pin "11") (pinfunction "AINP1_11") (pintype "bidirectional"))
    )
    (net (code "46") (name "Net-(U2-CAP1)") (class "Default")
      (node (ref "C2") (pin "2") (pinfunction "2_2") (pintype "passive"))
      (node (ref "U2") (pin "9") (pinfunction "CAP1_9") (pintype "bidirectional"))
    )
    (net (code "47") (name "Net-(U2-CAP2)") (class "Default")
      (node (ref "C2") (pin "1") (pinfunction "1_1") (pintype "passive"))
      (node (ref "U2") (pin "10") (pinfunction "CAP2_10") (pintype "bidirectional"))
    )
    (net (code "48") (name "Net-(U3-ISET)") (class "Default")
      (node (ref "R1") (pin "2") (pinfunction "2_2") (pintype "passive"))
      (node (ref "U3") (pin "4") (pinfunction "ISET_4") (pintype "bidirectional"))
    )
    (net (code "49") (name "Net-(U3-TS)") (class "Default")
      (node (ref "R2") (pin "1") (pinfunction "1_1") (pintype "passive"))
      (node (ref "U3") (pin "1") (pinfunction "TS_1") (pintype "bidirectional"))
    )
    (net (code "50") (name "Net-(U4-VOUT+)") (class "Default")
      (node (ref "C15") (pin "1") (pinfunction "1_1") (pintype "passive"))
      (node (ref "R21") (pin "1") (pinfunction "1_1") (pintype "passive"))
      (node (ref "U4") (pin "12") (pinfunction "VOUT+_12") (pintype "power_in"))
      (node (ref "U8") (pin "8") (pinfunction "IN_8") (pintype "power_in"))
    )
    (net (code "51") (name "Net-(U4-VOUT-)") (class "Default")
      (node (ref "C6") (pin "2") (pinfunction "2_2") (pintype "passive"))
      (node (ref "R22") (pin "1") (pinfunction "1_1") (pintype "passive"))
      (node (ref "U4") (pin "9") (pinfunction "VOUT-_9") (pintype "power_in"))
      (node (ref "U6") (pin "2") (pinfunction "VIN_2") (pintype "power_in"))
      (node (ref "U6") (pin "3") (pinfunction "VIN_3") (pintype "power_in"))
      (node (ref "U6") (pin "6") (pinfunction "VIN_6") (pintype "power_in"))
      (node (ref "U6") (pin "7") (pinfunction "VIN_7") (pintype "power_in"))
    )
    (net (code "52") (name "Net-(U5-AREF)") (class "Default")
      (node (ref "C9") (pin "1") (pinfunction "1_1") (pintype "passive"))
      (node (ref "U5") (pin "20") (pinfunction "AREF_20") (pintype "bidirectional"))
    )
    (net (code "53") (name "Net-(U5-PB6{slash}XTAL1)") (class "Default")
      (node (ref "C7") (pin "2") (pinfunction "2_2") (pintype "passive"))
      (node (ref "U5") (pin "7") (pinfunction "PB6/XTAL1_7") (pintype "bidirectional"))
      (node (ref "XTAL1") (pin "1") (pinfunction "P$1_1") (pintype "bidirectional"))
    )
    (net (code "54") (name "Net-(U5-PB7{slash}XTAL2)") (class "Default")
      (node (ref "C8") (pin "2") (pinfunction "2_2") (pintype "passive"))
      (node (ref "U5") (pin "8") (pinfunction "PB7/XTAL2_8") (pintype "bidirectional"))
      (node (ref "XTAL1") (pin "3") (pinfunction "P$2_3") (pintype "bidirectional"))
    )
    (net (code "55") (name "Net-(U6-SD{slash}CT)") (class "Default")
      (node (ref "C5") (pin "2") (pinfunction "2_2") (pintype "passive"))
      (node (ref "U6") (pin "8") (pinfunction "SD/CT_8") (pintype "bidirectional"))
    )
    (net (code "56") (name "Net-(U7-IO1)") (class "Default")
      (node (ref "R13") (pin "2") (pinfunction "2_2") (pintype "passive"))
      (node (ref "U7") (pin "1") (pinfunction "IO1_1") (pintype "bidirectional"))
      (node (ref "USB") (pin "A6") (pinfunction "DP1_A6_A6") (pintype "bidirectional"))
      (node (ref "USB") (pin "B6") (pinfunction "B6_DP2_B6") (pintype "bidirectional"))
    )
    (net (code "57") (name "Net-(U7-IO2)") (class "Default")
      (node (ref "R12") (pin "2") (pinfunction "2_2") (pintype "passive"))
      (node (ref "U7") (pin "3") (pinfunction "IO2_3") (pintype "bidirectional"))
      (node (ref "USB") (pin "A7") (pinfunction "DN1_A7_A7") (pintype "bidirectional"))
      (node (ref "USB") (pin "B7") (pinfunction "B7_DN2_B7") (pintype "bidirectional"))
    )
    (net (code "58") (name "Net-(U7-IO3)") (class "Default")
      (node (ref "F1") (pin "2") (pinfunction "2_2") (pintype "passive"))
      (node (ref "U7") (pin "4") (pinfunction "IO3_4") (pintype "bidirectional"))
      (node (ref "USB") (pin "A4") (pinfunction "VBUS_A4_A4") (pintype "power_in"))
      (node (ref "USB") (pin "A9") (pinfunction "VBUS_A9_A9") (pintype "power_in"))
      (node (ref "USB") (pin "B4") (pinfunction "B4_VBUS_B4") (pintype "power_in"))
      (node (ref "USB") (pin "B9") (pinfunction "B9_VBUS_B9") (pintype "power_in"))
    )
    (net (code "59") (name "Net-(U10-RXD)") (class "Default")
      (node (ref "D2") (pin "C") (pinfunction "C_C") (pintype "passive"))
      (node (ref "U10") (pin "4") (pinfunction "RXD_4") (pintype "bidirectional"))
    )
    (net (code "60") (name "Net-(U10-TXD)") (class "Default")
      (node (ref "D1") (pin "A") (pinfunction "A_A") (pintype "passive"))
      (node (ref "U10") (pin "1") (pinfunction "TXD_1") (pintype "bidirectional"))
    )
    (net (code "61") (name "Net-(U12-IN1-)") (class "Default")
      (node (ref "R5") (pin "2") (pinfunction "2_2") (pintype "passive"))
      (node (ref "U12") (pin "1") (pinfunction "OUT1_1") (pintype "bidirectional"))
      (node (ref "U12") (pin "2") (pinfunction "IN1-_2") (pintype "bidirectional"))
    )
    (net (code "62") (name "Net-(U12-IN2+)") (class "Default")
      (node (ref "R24") (pin "2") (pinfunction "2_2") (pintype "passive"))
      (node (ref "R25") (pin "1") (pinfunction "1_1") (pintype "passive"))
      (node (ref "U12") (pin "5") (pinfunction "IN2+_5") (pintype "bidirectional"))
    )
    (net (code "63") (name "Net-(U12-IN2-)") (class "Default")
      (node (ref "C1") (pin "1") (pinfunction "1_1") (pintype "passive"))
      (node (ref "U12") (pin "6") (pinfunction "IN2-_6") (pintype "bidirectional"))
      (node (ref "U12") (pin "7") (pinfunction "OUT2_7") (pintype "bidirectional"))
      (node (ref "U2") (pin "16") (pinfunction "REFP_16") (pintype "bidirectional"))
      (node (ref "U2") (pin "18") (pinfunction "AVDD_18") (pintype "power_in"))
    )
    (net (code "64") (name "Net-(USB-B5_CC2)") (class "Default")
      (node (ref "R15") (pin "2") (pinfunction "2_2") (pintype "passive"))
      (node (ref "USB") (pin "B5") (pinfunction "B5_CC2_B5") (pintype "bidirectional"))
    )
    (net (code "65") (name "Net-(USB-CC1_A5)") (class "Default")
      (node (ref "R14") (pin "2") (pinfunction "2_2") (pintype "passive"))
      (node (ref "USB") (pin "A5") (pinfunction "CC1_A5_A5") (pintype "bidirectional"))
    )
    (net (code "66") (name "V+") (class "Default")
      (node (ref "BAT") (pin "2") (pinfunction "2_2") (pintype "bidirectional"))
      (node (ref "Q4") (pin "2") (pinfunction "S_2") (pintype "passive"))
      (node (ref "Q5") (pin "3") (pinfunction "S_3") (pintype "passive"))
      (node (ref "R19") (pin "1") (pinfunction "1_1") (pintype "passive"))
      (node (ref "R7") (pin "2") (pinfunction "2_2") (pintype "passive"))
      (node (ref "U3") (pin "2") (pinfunction "VOUT_2") (pintype "power_in"))
    )
    (net (code "67") (name "VCC") (class "Default")
      (node (ref "C11") (pin "1") (pinfunction "1_1") (pintype "passive"))
      (node (ref "C17") (pin "1") (pinfunction "1_1") (pintype "passive"))
      (node (ref "LCD1") (pin "21") (pinfunction "VCC_21") (pintype "power_in"))
      (node (ref "LCD1") (pin "22") (pinfunction "VCC_22") (pintype "power_in"))
      (node (ref "LCD1") (pin "39") (pinfunction "VCC_39") (pintype "power_in"))
      (node (ref "LCD1") (pin "40") (pinfunction "VCC_40") (pintype "power_in"))
      (node (ref "R23") (pin "1") (pinfunction "1_1") (pintype "passive"))
      (node (ref "U9") (pin "5") (pinfunction "VOUT+_5") (pintype "power_in"))
    )
    (net (code "68") (name "unconnected-(LCD1-D2-Pad34)") (class "Default")
      (node (ref "LCD1") (pin "34") (pinfunction "D2_34") (pintype "bidirectional"))
    )
    (net (code "69") (name "unconnected-(U2-XTAL2-Pad4)") (class "Default")
      (node (ref "U2") (pin "4") (pinfunction "XTAL2_4") (pintype "bidirectional"))
    )
    (net (code "70") (name "unconnected-(U5-ADC6-Pad19)") (class "Default")
      (node (ref "U5") (pin "19") (pinfunction "ADC6_19") (pintype "bidirectional"))
    )
    (net (code "71") (name "unconnected-(U10-CBUS0-Pad15)") (class "Default")
      (node (ref "U10") (pin "15") (pinfunction "CBUS0_15") (pintype "bidirectional"))
    )
    (net (code "72") (name "unconnected-(U10-CBUS1-Pad14)") (class "Default")
      (node (ref "U10") (pin "14") (pinfunction "CBUS1_14") (pintype "bidirectional"))
    )
    (net (code "73") (name "unconnected-(U10-CBUS2-Pad7)") (class "Default")
      (node (ref "U10") (pin "7") (pinfunction "CBUS2_7") (pintype "bidirectional"))
    )
    (net (code "74") (name "unconnected-(U10-CBUS3-Pad16)") (class "Default")
      (node (ref "U10") (pin "16") (pinfunction "CBUS3_16") (pintype "bidirectional"))
    )
    (net (code "75") (name "unconnected-(U10-RTS'-Pad2)") (class "Default")
      (node (ref "U10") (pin "2") (pinfunction "RTS'_2") (pintype "bidirectional"))
    )
    (net (code "76") (name "unconnected-(USB-B2_SSTXP2-PadB2)") (class "Default")
      (node (ref "USB") (pin "B2") (pinfunction "B2_SSTXP2_B2") (pintype "bidirectional"))
    )
    (net (code "77") (name "unconnected-(USB-B3_SSTXN2-PadB3)") (class "Default")
      (node (ref "USB") (pin "B3") (pinfunction "B3_SSTXN2_B3") (pintype "bidirectional"))
    )
    (net (code "78") (name "unconnected-(USB-B8_SBU2-PadB8)") (class "Default")
      (node (ref "USB") (pin "B8") (pinfunction "B8_SBU2_B8") (pintype "bidirectional"))
    )
    (net (code "79") (name "unconnected-(USB-B10_SSRXN1-PadB10)") (class "Default")
      (node (ref "USB") (pin "B10") (pinfunction "B10_SSRXN1_B10") (pintype "bidirectional"))
    )
    (net (code "80") (name "unconnected-(USB-B11_SSRXP1-PadB11)") (class "Default")
      (node (ref "USB") (pin "B11") (pinfunction "B11_SSRXP1_B11") (pintype "bidirectional"))
    )
    (net (code "81") (name "unconnected-(USB-SBU1_A8-PadA8)") (class "Default")
      (node (ref "USB") (pin "A8") (pinfunction "SBU1_A8_A8") (pintype "bidirectional"))
    )
    (net (code "82") (name "unconnected-(USB-SSRXN2_A10-PadA10)") (class "Default")
      (node (ref "USB") (pin "A10") (pinfunction "SSRXN2_A10_A10") (pintype "bidirectional"))
    )
    (net (code "83") (name "unconnected-(USB-SSRXP2_A11-PadA11)") (class "Default")
      (node (ref "USB") (pin "A11") (pinfunction "SSRXP2_A11_A11") (pintype "bidirectional"))
    )
    (net (code "84") (name "unconnected-(USB-SSTXN1_A3-PadA3)") (class "Default")
      (node (ref "USB") (pin "A3") (pinfunction "SSTXN1_A3_A3") (pintype "bidirectional"))
    )
    (net (code "85") (name "unconnected-(USB-SSTXP1_A2-PadA2)") (class "Default")
      (node (ref "USB") (pin "A2") (pinfunction "SSTXP1_A2_A2") (pintype "bidirectional"))
    )
  )
)
